# try1.net
KiCad netlist of a schematic drawn in EAGLE
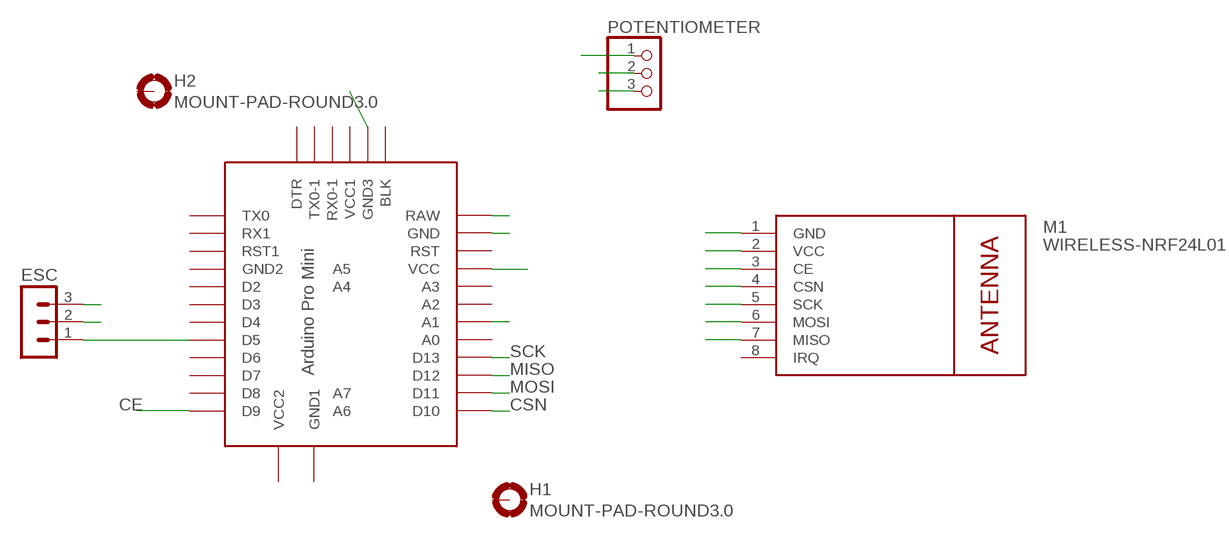
[diagram p0: schematic, sheet 1]

(export (version "E")
  (design (tool "Eeschema 10.0.6"))
  (components
    (comp (ref "ESC")
      (value "MA03-1")
      (footprint "eagle-import:MA03-1")
      (libsource (lib "eagle-import") (part "MA03-1"))
    )
    (comp (ref "H1")
      (value "MOUNT-PAD-ROUND3.0")
      (footprint "eagle-import:3,0-PAD")
      (libsource (lib "eagle-import") (part "MOUNT-PAD-ROUND3.0"))
    )
    (comp (ref "H2")
      (value "MOUNT-PAD-ROUND3.0")
      (footprint "eagle-import:3,0-PAD")
      (libsource (lib "eagle-import") (part "MOUNT-PAD-ROUND3.0"))
    )
    (comp (ref "M1")
      (value "WIRELESS-NRF24L01")
      (footprint "eagle-import:WIRELESS-NRF24L01")
      (libsource (lib "eagle-import") (part "WIRELESS-NRF24L01"))
    )
    (comp (ref "POTENTIOMETER")
      (value "PINHD-1X3")
      (footprint "eagle-import:1X03")
      (libsource (lib "eagle-import") (part "PINHD-1X3"))
    )
    (comp (ref "U$2")
      (value "PRO-MINI-33")
      (footprint "eagle-import:PRO-MINI-33")
      (libsource (lib "eagle-import") (part "PRO-MINI-33"))
    )
  )
  (nets
    (net (code "1") (name "/CE") (class "Default")
      (node (ref "M1") (pin "3") (pinfunction "CE_3") (pintype "bidirectional"))
      (node (ref "U$2") (pin "D9") (pinfunction "D9_D9") (pintype "bidirectional"))
    )
    (net (code "2") (name "/CSN") (class "Default")
      (node (ref "M1") (pin "4") (pinfunction "CSN_4") (pintype "bidirectional"))
      (node (ref "U$2") (pin "D10") (pinfunction "D10_D10") (pintype "bidirectional"))
    )
    (net (code "3") (name "/GND") (class "Default")
      (node (ref "ESC") (pin "3") (pinfunction "3_3") (pintype "passive"))
      (node (ref "M1") (pin "1") (pinfunction "GND_1") (pintype "power_in"))
      (node (ref "POTENTIOMETER") (pin "3") (pinfunction "3_3") (pintype "passive"))
      (node (ref "U$2") (pin "GND") (pinfunction "GND_GND") (pintype "bidirectional"))
      (node (ref "U$2") (pin "GND3") (pinfunction "GND3_GND3") (pintype "bidirectional"))
    )
    (net (code "4") (name "/MISO") (class "Default")
      (node (ref "M1") (pin "7") (pinfunction "MISO_7") (pintype "bidirectional"))
      (node (ref "U$2") (pin "D12") (pinfunction "D12_D12") (pintype "bidirectional"))
    )
    (net (code "5") (name "/MOSI") (class "Default")
      (node (ref "M1") (pin "6") (pinfunction "MOSI_6") (pintype "bidirectional"))
      (node (ref "U$2") (pin "D11") (pinfunction "D11_D11") (pintype "bidirectional"))
    )
    (net (code "6") (name "/RAW") (class "Default")
      (node (ref "ESC") (pin "2") (pinfunction "2_2") (pintype "passive"))
      (node (ref "U$2") (pin "RAW") (pinfunction "RAW_RAW") (pintype "bidirectional"))
    )
    (net (code "7") (name "/SCK") (class "Default")
      (node (ref "M1") (pin "5") (pinfunction "SCK_5") (pintype "bidirectional"))
      (node (ref "U$2") (pin "D13") (pinfunction "D13_D13") (pintype "bidirectional"))
    )
    (net (code "8") (name "/SIG") (class "Default")
      (node (ref "ESC") (pin "1") (pinfunction "1_1") (pintype "passive"))
      (node (ref "POTENTIOMETER") (pin "1") (pinfunction "1_1") (pintype "passive"))
      (node (ref "U$2") (pin "A1") (pinfunction "A1_A1") (pintype "bidirectional"))
      (node (ref "U$2") (pin "D5") (pinfunction "D5_D5") (pintype "bidirectional"))
    )
    (net (code "9") (name "/VCC") (class "Default")
      (node (ref "M1") (pin "2") (pinfunction "VCC_2") (pintype "power_in"))
      (node (ref "POTENTIOMETER") (pin "2") (pinfunction "2_2") (pintype "passive"))
      (node (ref "U$2") (pin "VCC") (pinfunction "VCC_VCC") (pintype "bidirectional"))
    )
    (net (code "10") (name "unconnected-(H1-MOUNT-PadB3,0)") (class "Default")
      (node (ref "H1") (pin "B3,0") (pinfunction "MOUNT_B3,0") (pintype "passive"))
    )
    (net (code "11") (name "unconnected-(H2-MOUNT-PadB3,0)") (class "Default")
      (node (ref "H2") (pin "B3,0") (pinfunction "MOUNT_B3,0") (pintype "passive"))
    )
    (net (code "12") (name "unconnected-(M1-IRQ-Pad8)") (class "Default")
      (node (ref "M1") (pin "8") (pinfunction "IRQ_8") (pintype "bidirectional"))
    )
    (net (code "13") (name "unconnected-(U$2-PadA0)") (class "Default")
      (node (ref "U$2") (pin "A0") (pinfunction "A0_A0") (pintype "bidirectional"))
    )
    (net (code "14") (name "unconnected-(U$2-PadA2)") (class "Default")
      (node (ref "U$2") (pin "A2") (pinfunction "A2_A2") (pintype "bidirectional"))
    )
    (net (code "15") (name "unconnected-(U$2-PadA3)") (class "Default")
      (node (ref "U$2") (pin "A3") (pinfunction "A3_A3") (pintype "bidirectional"))
    )
    (net (code "16") (name "unconnected-(U$2-PadA4)") (class "Default")
      (node (ref "U$2") (pin "A4") (pinfunction "A4_A4") (pintype "bidirectional"))
    )
    (net (code "17") (name "unconnected-(U$2-PadA5)") (class "Default")
      (node (ref "U$2") (pin "A5") (pinfunction "A5_A5") (pintype "bidirectional"))
    )
    (net (code "18") (name "unconnected-(U$2-PadA6)") (class "Default")
      (node (ref "U$2") (pin "A6") (pinfunction "A6_A6") (pintype "bidirectional"))
    )
    (net (code "19") (name "unconnected-(U$2-PadA7)") (class "Default")
      (node (ref "U$2") (pin "A7") (pinfunction "A7_A7") (pintype "bidirectional"))
    )
    (net (code "20") (name "unconnected-(U$2-PadBLK)") (class "Default")
      (node (ref "U$2") (pin "BLK") (pinfunction "BLK_BLK") (pintype "bidirectional"))
    )
    (net (code "21") (name "unconnected-(U$2-PadD2)") (class "Default")
      (node (ref "U$2") (pin "D2") (pinfunction "D2_D2") (pintype "bidirectional"))
    )
    (net (code "22") (name "unconnected-(U$2-PadD3)") (class "Default")
      (node (ref "U$2") (pin "D3") (pinfunction "D3_D3") (pintype "bidirectional"))
    )
    (net (code "23") (name "unconnected-(U$2-PadD4)") (class "Default")
      (node (ref "U$2") (pin "D4") (pinfunction "D4_D4") (pintype "bidirectional"))
    )
    (net (code "24") (name "unconnected-(U$2-PadD6)") (class "Default")
      (node (ref "U$2") (pin "D6") (pinfunction "D6_D6") (pintype "bidirectional"))
    )
    (net (code "25") (name "unconnected-(U$2-PadD7)") (class "Default")
      (node (ref "U$2") (pin "D7") (pinfunction "D7_D7") (pintype "bidirectional"))
    )
    (net (code "26") (name "unconnected-(U$2-PadD8)") (class "Default")
      (node (ref "U$2") (pin "D8") (pinfunction "D8_D8") (pintype "bidirectional"))
    )
    (net (code "27") (name "unconnected-(U$2-PadDTR)") (class "Default")
      (node (ref "U$2") (pin "DTR") (pinfunction "DTR_DTR") (pintype "bidirectional"))
    )
    (net (code "28") (name "unconnected-(U$2-PadGND1)") (class "Default")
      (node (ref "U$2") (pin "GND1") (pinfunction "GND1_GND1") (pintype "bidirectional"))
    )
    (net (code "29") (name "unconnected-(U$2-PadGND2)") (class "Default")
      (node (ref "U$2") (pin "GND2") (pinfunction "GND2_GND2") (pintype "bidirectional"))
    )
    (net (code "30") (name "unconnected-(U$2-PadRST)") (class "Default")
      (node (ref "U$2") (pin "RST") (pinfunction "RST_RST") (pintype "bidirectional"))
    )
    (net (code "31") (name "unconnected-(U$2-PadRST1)") (class "Default")
      (node (ref "U$2") (pin "RST1") (pinfunction "RST1_RST1") (pintype "bidirectional"))
    )
    (net (code "32") (name "unconnected-(U$2-PadRX0-1)") (class "Default")
      (node (ref "U$2") (pin "RX0-1") (pinfunction "RX0-1_RX0-1") (pintype "bidirectional"))
    )
    (net (code "33") (name "unconnected-(U$2-PadRX1)") (class "Default")
      (node (ref "U$2") (pin "RX1") (pinfunction "RX1_RX1") (pintype "bidirectional"))
    )
    (net (code "34") (name "unconnected-(U$2-PadTX0)") (class "Default")
      (node (ref "U$2") (pin "TX0") (pinfunction "TX0_TX0") (pintype "bidirectional"))
    )
    (net (code "35") (name "unconnected-(U$2-PadTX0-1)") (class "Default")
      (node (ref "U$2") (pin "TX0-1") (pinfunction "TX0-1_TX0-1") (pintype "bidirectional"))
    )
    (net (code "36") (name "unconnected-(U$2-PadVCC1)") (class "Default")
      (node (ref "U$2") (pin "VCC1") (pinfunction "VCC1_VCC1") (pintype "bidirectional"))
    )
    (net (code "37") (name "unconnected-(U$2-PadVCC2)") (class "Default")
      (node (ref "U$2") (pin "VCC2") (pinfunction "VCC2_VCC2") (pintype "bidirectional"))
    )
  )
)
